# wsmodule.net
KiCad netlist of a schematic drawn in EAGLE
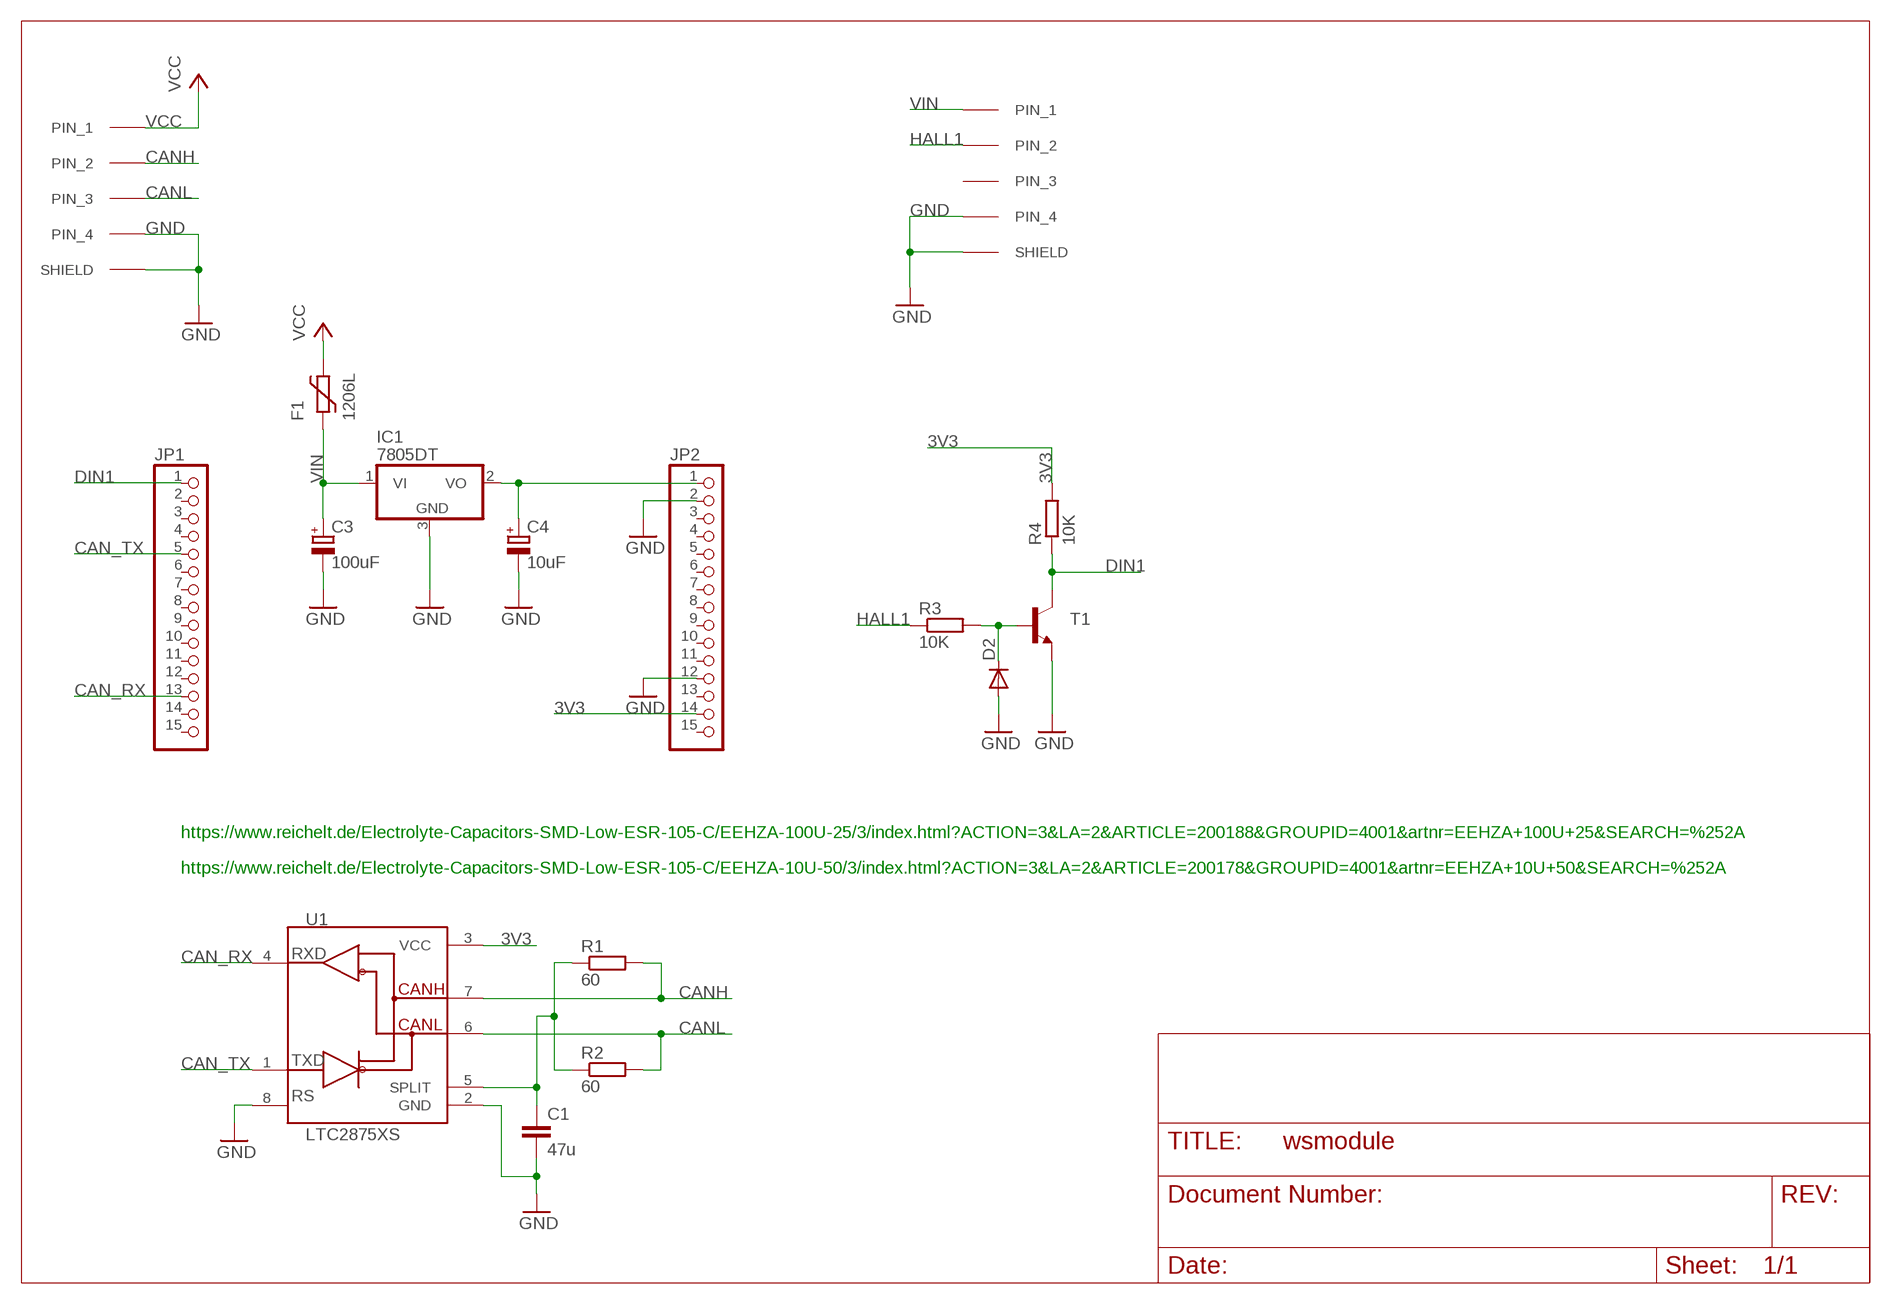
[diagram p0: schematic, sheet 1]

(export (version "E")
  (design (tool "Eeschema 10.0.6"))
  (components
    (comp (ref "C1")
      (value "47u")
      (footprint "eagle-import:C1210")
      (libsource (lib "eagle-import") (part "CC1210"))
    )
    (comp (ref "C3")
      (value "100uF")
      (footprint "eagle-import:PANASONIC_D")
      (libsource (lib "eagle-import") (part "CPOL-EUD"))
    )
    (comp (ref "C4")
      (value "10uF")
      (footprint "eagle-import:PANASONIC_C")
      (libsource (lib "eagle-import") (part "CPOL-EUC"))
    )
    (comp (ref "D2")
      (value "DIODE-GF1")
      (footprint "eagle-import:GF1")
      (libsource (lib "eagle-import") (part "DIODE-GF1"))
    )
    (comp (ref "F1")
      (value "1206L")
      (footprint "eagle-import:1206L")
      (libsource (lib "eagle-import") (part "1206L"))
    )
    (comp (ref "IC1")
      (value "7805DT")
      (footprint "eagle-import:TO252")
      (libsource (lib "eagle-import") (part "78DT05"))
    )
    (comp (ref "INPUT")
      (value "M8-718-MALE")
      (footprint "eagle-import:M18-718-MALE")
      (libsource (lib "eagle-import") (part "M8-718-MALE"))
    )
    (comp (ref "JP1")
      (value "PINHD-1X15")
      (footprint "eagle-import:1X15")
      (libsource (lib "eagle-import") (part "PINHD-1X15"))
    )
    (comp (ref "JP2")
      (value "PINHD-1X15")
      (footprint "eagle-import:1X15")
      (libsource (lib "eagle-import") (part "PINHD-1X15"))
    )
    (comp (ref "OUTPUT")
      (value "M8-718-FEMALE")
      (footprint "eagle-import:M18-718-FEMALE")
      (libsource (lib "eagle-import") (part "M8-718-FEMALE"))
    )
    (comp (ref "R1")
      (value "60")
      (footprint "eagle-import:R1206")
      (libsource (lib "eagle-import") (part "RR1206"))
    )
    (comp (ref "R2")
      (value "60")
      (footprint "eagle-import:R1206")
      (libsource (lib "eagle-import") (part "RR1206"))
    )
    (comp (ref "R3")
      (value "10K")
      (footprint "eagle-import:R1206")
      (libsource (lib "eagle-import") (part "RR1206"))
    )
    (comp (ref "R4")
      (value "10K")
      (footprint "eagle-import:R1206")
      (libsource (lib "eagle-import") (part "RR1206"))
    )
    (comp (ref "T1")
      (value "BC849")
      (footprint "eagle-import:SOT23")
      (libsource (lib "eagle-import") (part "BC849"))
    )
    (comp (ref "U1")
      (value "LTC2875XS")
      (footprint "eagle-import:SO-08")
      (libsource (lib "eagle-import") (part "LTC2875XS"))
    )
  )
  (nets
    (net (code "1") (name "/3V3") (class "Default")
      (node (ref "JP2") (pin "14") (pinfunction "14_14") (pintype "passive"))
      (node (ref "R4") (pin "2") (pinfunction "2_2") (pintype "passive"))
      (node (ref "U1") (pin "3") (pinfunction "VCC_3") (pintype "bidirectional"))
    )
    (net (code "2") (name "/CANH") (class "Default")
      (node (ref "INPUT") (pin "P$2") (pinfunction "PIN_2_P$2") (pintype "bidirectional"))
      (node (ref "R1") (pin "2") (pinfunction "2_2") (pintype "passive"))
      (node (ref "U1") (pin "7") (pinfunction "CANH_7") (pintype "bidirectional"))
    )
    (net (code "3") (name "/CANL") (class "Default")
      (node (ref "INPUT") (pin "P$3") (pinfunction "PIN_3_P$3") (pintype "bidirectional"))
      (node (ref "R2") (pin "2") (pinfunction "2_2") (pintype "passive"))
      (node (ref "U1") (pin "6") (pinfunction "CANL_6") (pintype "bidirectional"))
    )
    (net (code "4") (name "/CAN_RX") (class "Default")
      (node (ref "JP1") (pin "13") (pinfunction "13_13") (pintype "passive"))
      (node (ref "U1") (pin "4") (pinfunction "RXD_4") (pintype "bidirectional"))
    )
    (net (code "5") (name "/CAN_TX") (class "Default")
      (node (ref "JP1") (pin "5") (pinfunction "5_5") (pintype "passive"))
      (node (ref "U1") (pin "1") (pinfunction "TXD_1") (pintype "bidirectional"))
    )
    (net (code "6") (name "/DIN1") (class "Default")
      (node (ref "JP1") (pin "1") (pinfunction "1_1") (pintype "passive"))
      (node (ref "R4") (pin "1") (pinfunction "1_1") (pintype "passive"))
      (node (ref "T1") (pin "3") (pinfunction "C_3") (pintype "passive"))
    )
    (net (code "7") (name "/HALL1") (class "Default")
      (node (ref "OUTPUT") (pin "P$2") (pinfunction "PIN_2_P$2") (pintype "bidirectional"))
      (node (ref "R3") (pin "1") (pinfunction "1_1") (pintype "passive"))
    )
    (net (code "8") (name "/VIN") (class "Default")
      (node (ref "C3") (pin "+") (pinfunction "+_+") (pintype "passive"))
      (node (ref "F1") (pin "P$1") (pinfunction "1_P$1") (pintype "passive"))
      (node (ref "IC1") (pin "1") (pinfunction "VI_1") (pintype "input"))
      (node (ref "OUTPUT") (pin "P$1") (pinfunction "PIN_1_P$1") (pintype "bidirectional"))
    )
    (net (code "9") (name "GND") (class "Default")
      (node (ref "C1") (pin "2") (pinfunction "2_2") (pintype "passive"))
      (node (ref "C3") (pin "-") (pinfunction "-_-") (pintype "passive"))
      (node (ref "C4") (pin "-") (pinfunction "-_-") (pintype "passive"))
      (node (ref "D2") (pin "A") (pinfunction "A_A") (pintype "passive"))
      (node (ref "IC1") (pin "3") (pinfunction "GND_3") (pintype "passive"))
      (node (ref "INPUT") (pin "L") (pinfunction "SHIELD_L") (pintype "bidirectional"))
      (node (ref "INPUT") (pin "P$4") (pinfunction "PIN_4_P$4") (pintype "bidirectional"))
      (node (ref "INPUT") (pin "R") (pinfunction "SHIELD_R") (pintype "bidirectional"))
      (node (ref "JP2") (pin "12") (pinfunction "12_12") (pintype "passive"))
      (node (ref "JP2") (pin "2") (pinfunction "2_2") (pintype "passive"))
      (node (ref "OUTPUT") (pin "L") (pinfunction "SHIELD_L") (pintype "bidirectional"))
      (node (ref "OUTPUT") (pin "P$4") (pinfunction "PIN_4_P$4") (pintype "bidirectional"))
      (node (ref "OUTPUT") (pin "R") (pinfunction "SHIELD_R") (pintype "bidirectional"))
      (node (ref "T1") (pin "2") (pinfunction "E_2") (pintype "passive"))
      (node (ref "U1") (pin "2") (pinfunction "GND_2") (pintype "bidirectional"))
      (node (ref "U1") (pin "8") (pinfunction "RS1_8") (pintype "bidirectional"))
    )
    (net (code "10") (name "Net-(IC1-VO)") (class "Default")
      (node (ref "C4") (pin "+") (pinfunction "+_+") (pintype "passive"))
      (node (ref "IC1") (pin "2") (pinfunction "VO_2") (pintype "passive"))
      (node (ref "JP2") (pin "1") (pinfunction "1_1") (pintype "passive"))
    )
    (net (code "11") (name "Net-(T1-B)") (class "Default")
      (node (ref "D2") (pin "C") (pinfunction "C_C") (pintype "passive"))
      (node (ref "R3") (pin "2") (pinfunction "2_2") (pintype "passive"))
      (node (ref "T1") (pin "1") (pinfunction "B_1") (pintype "passive"))
    )
    (net (code "12") (name "Net-(U1-SPLIT)") (class "Default")
      (node (ref "C1") (pin "1") (pinfunction "1_1") (pintype "passive"))
      (node (ref "R1") (pin "1") (pinfunction "1_1") (pintype "passive"))
      (node (ref "R2") (pin "1") (pinfunction "1_1") (pintype "passive"))
      (node (ref "U1") (pin "5") (pinfunction "SPLIT_5") (pintype "bidirectional"))
    )
    (net (code "13") (name "VCC") (class "Default")
      (node (ref "F1") (pin "P$2") (pinfunction "2_P$2") (pintype "passive"))
      (node (ref "INPUT") (pin "P$1") (pinfunction "PIN_1_P$1") (pintype "bidirectional"))
    )
    (net (code "14") (name "unconnected-(JP1-Pad2)") (class "Default")
      (node (ref "JP1") (pin "2") (pinfunction "2_2") (pintype "passive"))
    )
    (net (code "15") (name "unconnected-(JP1-Pad3)") (class "Default")
      (node (ref "JP1") (pin "3") (pinfunction "3_3") (pintype "passive"))
    )
    (net (code "16") (name "unconnected-(JP1-Pad4)") (class "Default")
      (node (ref "JP1") (pin "4") (pinfunction "4_4") (pintype "passive"))
    )
    (net (code "17") (name "unconnected-(JP1-Pad6)") (class "Default")
      (node (ref "JP1") (pin "6") (pinfunction "6_6") (pintype "passive"))
    )
    (net (code "18") (name "unconnected-(JP1-Pad7)") (class "Default")
      (node (ref "JP1") (pin "7") (pinfunction "7_7") (pintype "passive"))
    )
    (net (code "19") (name "unconnected-(JP1-Pad8)") (class "Default")
      (node (ref "JP1") (pin "8") (pinfunction "8_8") (pintype "passive"))
    )
    (net (code "20") (name "unconnected-(JP1-Pad9)") (class "Default")
      (node (ref "JP1") (pin "9") (pinfunction "9_9") (pintype "passive"))
    )
    (net (code "21") (name "unconnected-(JP1-Pad10)") (class "Default")
      (node (ref "JP1") (pin "10") (pinfunction "10_10") (pintype "passive"))
    )
    (net (code "22") (name "unconnected-(JP1-Pad11)") (class "Default")
      (node (ref "JP1") (pin "11") (pinfunction "11_11") (pintype "passive"))
    )
    (net (code "23") (name "unconnected-(JP1-Pad12)") (class "Default")
      (node (ref "JP1") (pin "12") (pinfunction "12_12") (pintype "passive"))
    )
    (net (code "24") (name "unconnected-(JP1-Pad14)") (class "Default")
      (node (ref "JP1") (pin "14") (pinfunction "14_14") (pintype "passive"))
    )
    (net (code "25") (name "unconnected-(JP1-Pad15)") (class "Default")
      (node (ref "JP1") (pin "15") (pinfunction "15_15") (pintype "passive"))
    )
    (net (code "26") (name "unconnected-(JP2-Pad3)") (class "Default")
      (node (ref "JP2") (pin "3") (pinfunction "3_3") (pintype "passive"))
    )
    (net (code "27") (name "unconnected-(JP2-Pad4)") (class "Default")
      (node (ref "JP2") (pin "4") (pinfunction "4_4") (pintype "passive"))
    )
    (net (code "28") (name "unconnected-(JP2-Pad5)") (class "Default")
      (node (ref "JP2") (pin "5") (pinfunction "5_5") (pintype "passive"))
    )
    (net (code "29") (name "unconnected-(JP2-Pad6)") (class "Default")
      (node (ref "JP2") (pin "6") (pinfunction "6_6") (pintype "passive"))
    )
    (net (code "30") (name "unconnected-(JP2-Pad7)") (class "Default")
      (node (ref "JP2") (pin "7") (pinfunction "7_7") (pintype "passive"))
    )
    (net (code "31") (name "unconnected-(JP2-Pad8)") (class "Default")
      (node (ref "JP2") (pin "8") (pinfunction "8_8") (pintype "passive"))
    )
    (net (code "32") (name "unconnected-(JP2-Pad9)") (class "Default")
      (node (ref "JP2") (pin "9") (pinfunction "9_9") (pintype "passive"))
    )
    (net (code "33") (name "unconnected-(JP2-Pad10)") (class "Default")
      (node (ref "JP2") (pin "10") (pinfunction "10_10") (pintype "passive"))
    )
    (net (code "34") (name "unconnected-(JP2-Pad11)") (class "Default")
      (node (ref "JP2") (pin "11") (pinfunction "11_11") (pintype "passive"))
    )
    (net (code "35") (name "unconnected-(JP2-Pad13)") (class "Default")
      (node (ref "JP2") (pin "13") (pinfunction "13_13") (pintype "passive"))
    )
    (net (code "36") (name "unconnected-(JP2-Pad15)") (class "Default")
      (node (ref "JP2") (pin "15") (pinfunction "15_15") (pintype "passive"))
    )
    (net (code "37") (name "unconnected-(OUTPUT-PIN_3-PadP$3)") (class "Default")
      (node (ref "OUTPUT") (pin "P$3") (pinfunction "PIN_3_P$3") (pintype "bidirectional"))
    )
  )
)
